# gemschematic_Chris_edits.net
KiCad netlist of a schematic drawn in Altium Designer
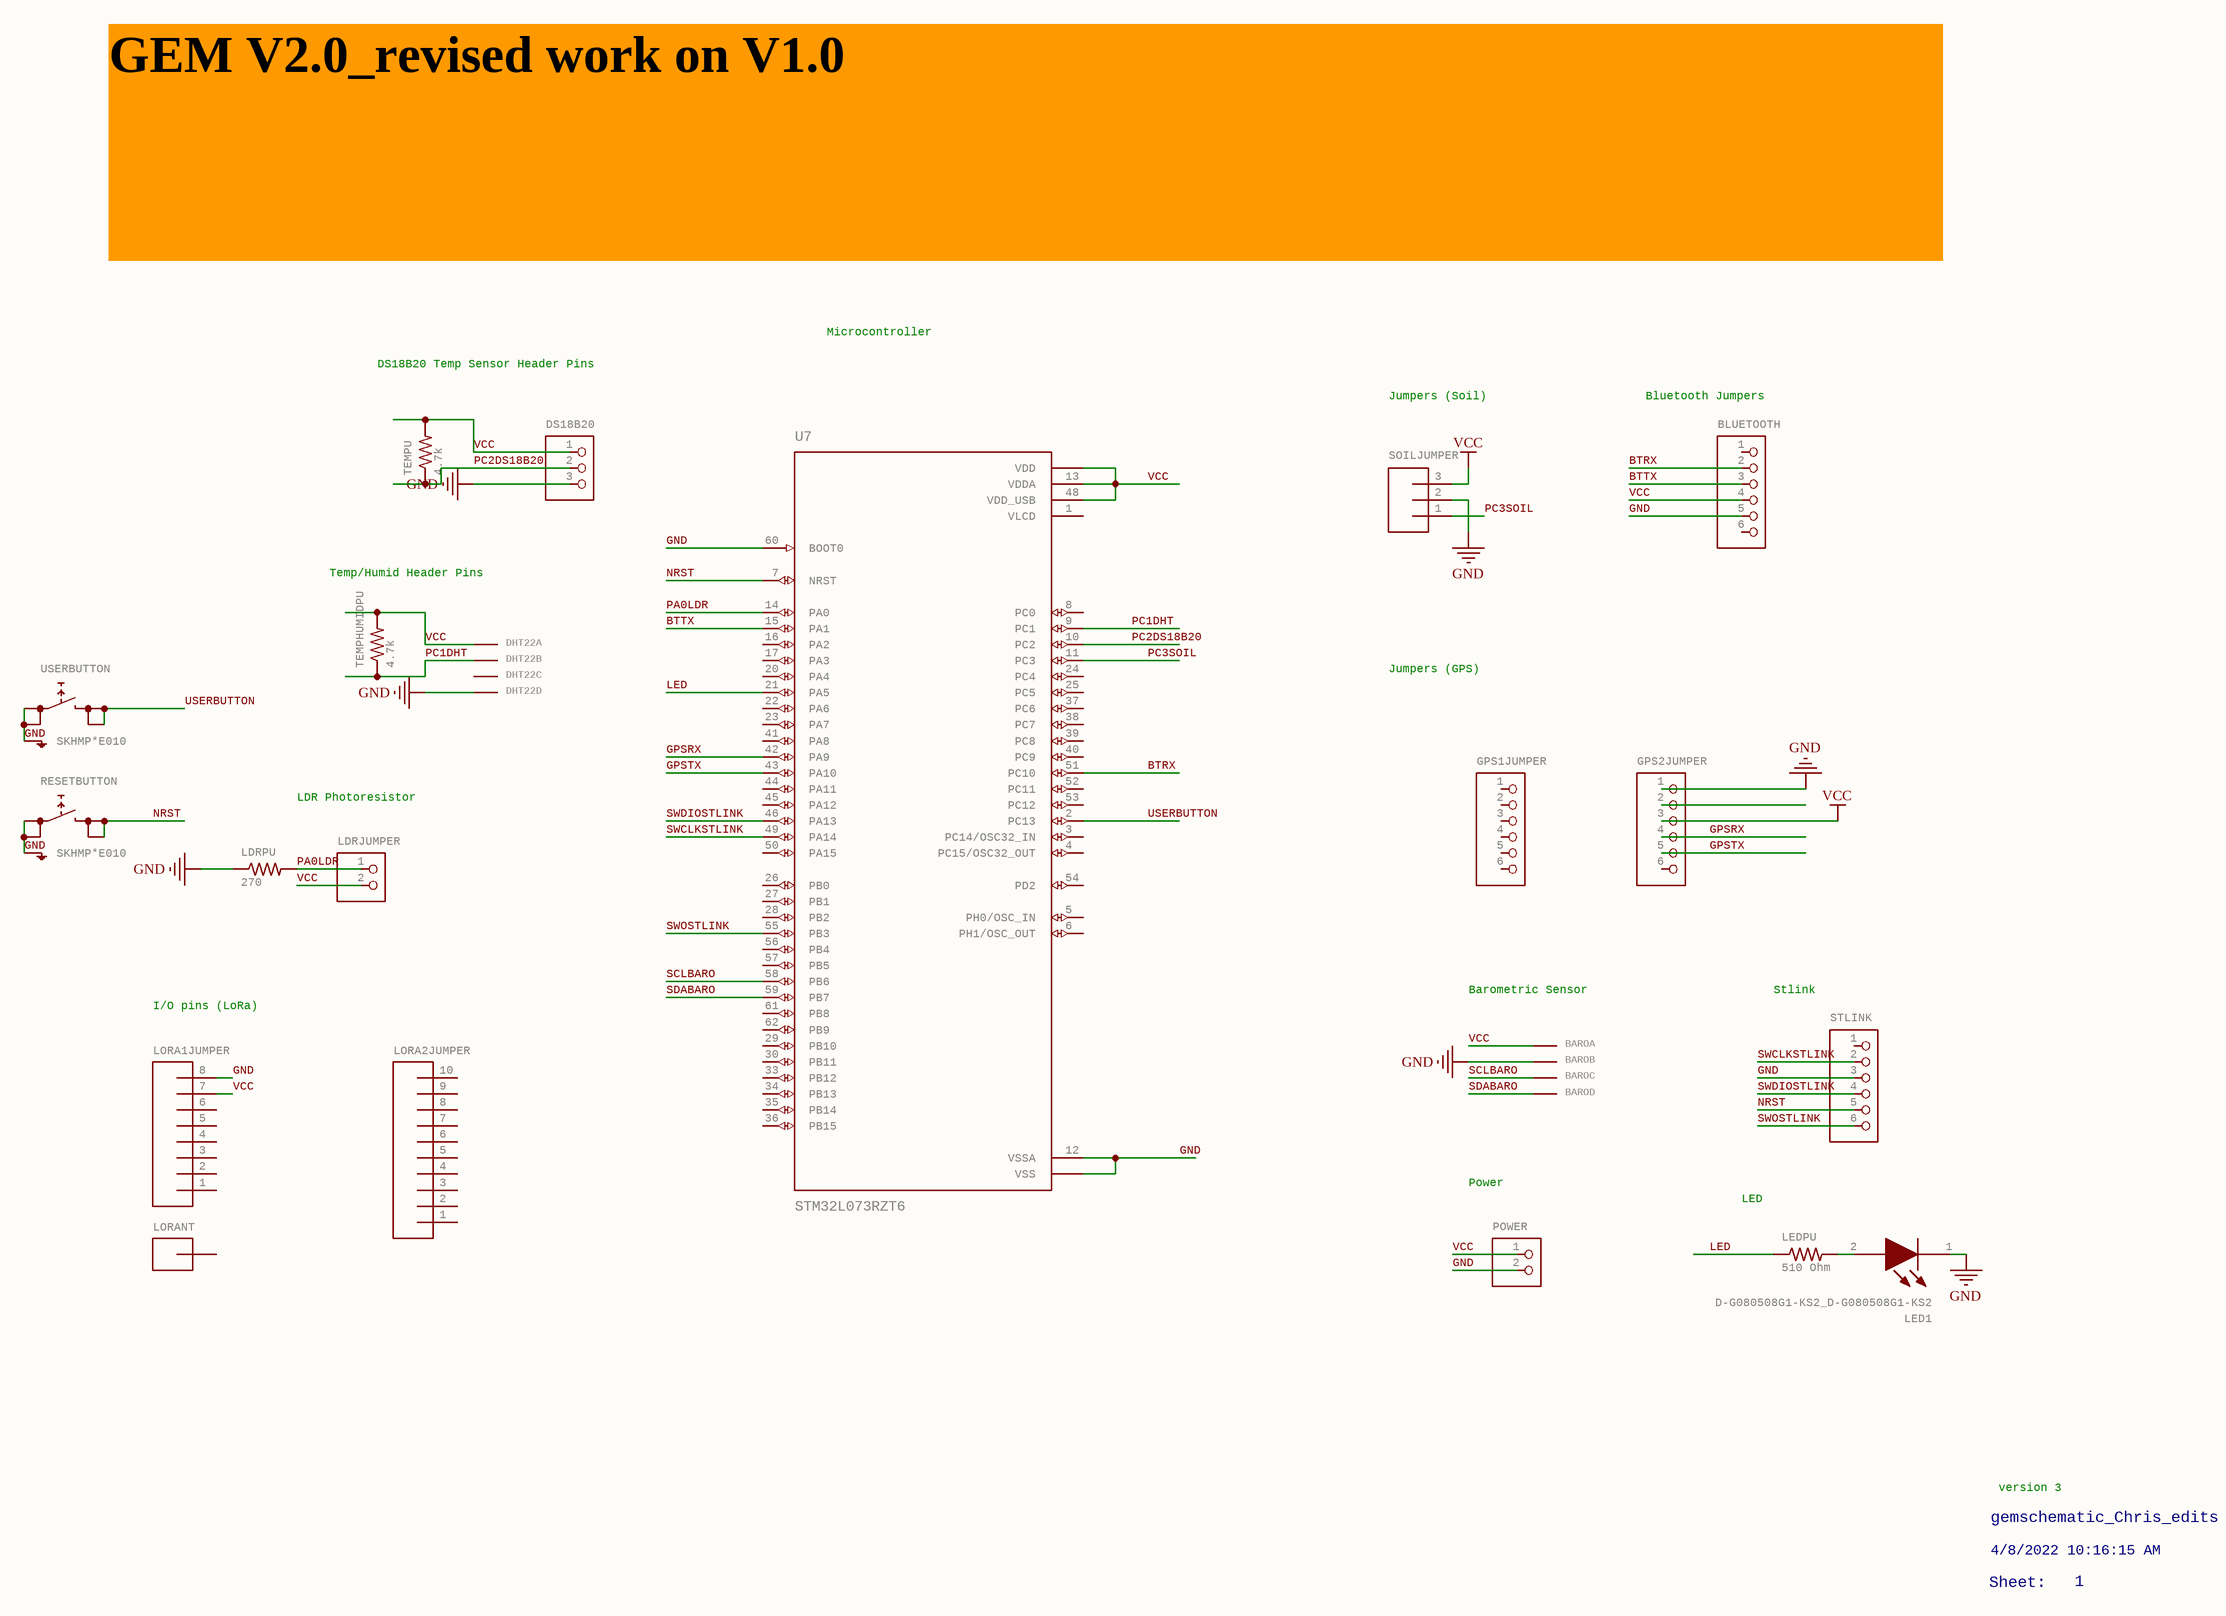
[diagram p0: gemschematic_Chris_edits.SchDoc]

(export (version "E")
  (design (tool "Eeschema 10.0.6"))
  (components
    (comp (ref "BARO")
      (value "22-23-2041")
      (footprint "22-23-2041")
      (description ".100\" (2.54mm) Center Header - 4 Pin")
      (fields (field (name "MF") "MOLEX"))
      (libsource (lib "con-molex") (part "22-23-2041"))
    )
    (comp (ref "BLUETOOTH")
      (value "PINHD-1X6")
      (footprint "1X06")
      (description "PIN HEADER")
      (libsource (lib "adafruit") (part "PINHD-1X6"))
    )
    (comp (ref "DHT22")
      (value "22-23-2041")
      (footprint "22-23-2041")
      (description ".100\" (2.54mm) Center Header - 4 Pin")
      (fields (field (name "MF") "MOLEX"))
      (libsource (lib "con-molex") (part "22-23-2041"))
    )
    (comp (ref "DS18B20")
      (value "PINHD-1X3")
      (footprint "1X03")
      (description "PIN HEADER")
      (libsource (lib "adafruit") (part "PINHD-1X3"))
    )
    (comp (ref "GPS1JUMPER")
      (value "HEADER-1X670MIL")
      (footprint "1X06_ROUND_70")
      (description "PIN HEADER")
      (libsource (lib "microbuilder") (part "HEADER-1X670MIL"))
    )
    (comp (ref "GPS2JUMPER")
      (value "HEADER-1X670MIL")
      (footprint "1X06_ROUND_70")
      (description "PIN HEADER")
      (libsource (lib "microbuilder") (part "HEADER-1X670MIL"))
    )
    (comp (ref "LDRJUMPER")
      (value "PINHD-1X2")
      (footprint "1X02")
      (description "PIN HEADER")
      (fields (field (name "LIBRARYNAME") "pinhead"))
      (libsource (lib "pinhead") (part "PINHD-1X2"))
    )
    (comp (ref "LDRPU")
      (value "270")
      (footprint "M0805")
      (description "RESISTOR, American symbol")
      (libsource (lib "adafruit") (part "R-US_M0805"))
    )
    (comp (ref "LED1")
      (value "D-G080508G1-KS2_D-G080508G1-KS2")
      (footprint "D-G080508G1-KS2_LEDC2012X85N")
      (description "Light Emitting Diodes (LED) Green 526~531nm 250~330mcd@5mA Top View 0805 RoHS   Source:  Datasheet")
      (fields
        (field (name "ARROW_PART_NUMBER") "ARROW_PART_NUMBER")
        (field (name "MANUFACTURER_PART_NUMBER") "D-G080508G1-KS2")
        (field (name "LIBRARYNAME") "ce-capstone-2022")
      )
      (libsource (lib "ce-capstone-2022") (part "D-G080508G1-KS2_D-G080508G1-KS2"))
    )
    (comp (ref "LEDPU")
      (value "510 Ohm")
      (footprint "M0805")
      (description "RESISTOR, American symbol")
      (libsource (lib "adafruit") (part "R-US_M0805"))
    )
    (comp (ref "LORA1JUMPER")
      (value "CONN_08NO_SILK_FEMALE_PTH")
      (footprint "1X08_NO_SILK")
      (libsource (lib "SparkFun-Connectors") (part "CONN_08NO_SILK_FEMALE_PTH"))
    )
    (comp (ref "LORA2JUMPER")
      (value "CONN_10NO_SILK_PTH_FEMALE")
      (footprint "1X10_NO_SILK")
      (libsource (lib "SparkFun-Connectors") (part "CONN_10NO_SILK_PTH_FEMALE"))
    )
    (comp (ref "LORANT")
      (value "CONN_01PTH_NO_SILK_YES_STOP")
      (footprint "1X01_NO_SILK")
      (libsource (lib "SparkFun-Connectors") (part "CONN_01PTH_NO_SILK_YES_STOP"))
    )
    (comp (ref "POWER")
      (value "PINHD-1X2")
      (footprint "1X02")
      (description "PIN HEADER")
      (fields (field (name "LIBRARYNAME") "pinhead"))
      (libsource (lib "pinhead") (part "PINHD-1X2"))
    )
    (comp (ref "RESETBUTTON")
      (value "SKHMP*E010")
      (footprint "SKHMPXE010")
      (libsource (lib "switch") (part "SKHMP*E010"))
    )
    (comp (ref "SOILJUMPER")
      (value "M03SCREW_LOCK")
      (footprint "SCREWTERMINAL-3.5MM-3_LOCK.007S")
      (libsource (lib "SparkFun-Connectors") (part "M03SCREW_LOCK"))
    )
    (comp (ref "STLINK")
      (value "PINHD-1X6")
      (footprint "1X06")
      (description "PIN HEADER")
      (libsource (lib "adafruit") (part "PINHD-1X6"))
    )
    (comp (ref "TEMPHUMIDPU")
      (value "4.7k")
      (footprint "M0805")
      (description "RESISTOR, American symbol")
      (libsource (lib "adafruit") (part "R-US_M0805"))
    )
    (comp (ref "TEMPU")
      (value "4.7k")
      (footprint "M0805")
      (description "RESISTOR, American symbol")
      (libsource (lib "adafruit") (part "R-US_M0805"))
    )
    (comp (ref "U7")
      (value "STM32L073RZT6")
      (footprint "QFP50P1200X1200X160-64N")
      (description "None Check availability")
      (fields (field (name "MF") "STMicroelectronics"))
      (libsource (lib "STM32L073RZT6") (part "STM32L073RZT6"))
    )
    (comp (ref "USERBUTTON")
      (value "SKHMP*E010")
      (footprint "SKHMPXE010")
      (libsource (lib "switch") (part "SKHMP*E010"))
    )
  )
  (nets
    (net (code "1") (name "/BTRX") (class "Default")
      (node (ref "BLUETOOTH") (pin "2") (pinfunction "2_2") (pintype "passive"))
      (node (ref "U7") (pin "51") (pinfunction "PC10_51") (pintype "bidirectional"))
    )
    (net (code "2") (name "/BTTX") (class "Default")
      (node (ref "BLUETOOTH") (pin "3") (pinfunction "3_3") (pintype "passive"))
      (node (ref "U7") (pin "15") (pinfunction "PA1_15") (pintype "bidirectional"))
    )
    (net (code "3") (name "/GPSRX") (class "Default")
      (node (ref "GPS2JUMPER") (pin "4") (pinfunction "4_4") (pintype "passive"))
      (node (ref "U7") (pin "42") (pinfunction "PA9_42") (pintype "bidirectional"))
    )
    (net (code "4") (name "/GPSTX") (class "Default")
      (node (ref "GPS2JUMPER") (pin "5") (pinfunction "5_5") (pintype "passive"))
      (node (ref "U7") (pin "43") (pinfunction "PA10_43") (pintype "bidirectional"))
    )
    (net (code "5") (name "/LED") (class "Default")
      (node (ref "LEDPU") (pin "1") (pinfunction "1_1") (pintype "passive"))
      (node (ref "U7") (pin "21") (pinfunction "PA5_21") (pintype "bidirectional"))
    )
    (net (code "6") (name "/NRST") (class "Default")
      (node (ref "RESETBUTTON") (pin "3") (pinfunction "2.1_3") (pintype "passive"))
      (node (ref "RESETBUTTON") (pin "4") (pinfunction "2.2_4") (pintype "passive"))
      (node (ref "STLINK") (pin "5") (pinfunction "5_5") (pintype "passive"))
      (node (ref "U7") (pin "7") (pinfunction "NRST_7") (pintype "bidirectional"))
    )
    (net (code "7") (name "/PA0LDR") (class "Default")
      (node (ref "LDRJUMPER") (pin "1") (pinfunction "1_1") (pintype "passive"))
      (node (ref "LDRPU") (pin "2") (pinfunction "2_2") (pintype "passive"))
      (node (ref "U7") (pin "14") (pinfunction "PA0_14") (pintype "bidirectional"))
    )
    (net (code "8") (name "/PC1DHT") (class "Default")
      (node (ref "DHT22") (pin "2") (pinfunction "S_2") (pintype "passive"))
      (node (ref "TEMPHUMIDPU") (pin "1") (pinfunction "1_1") (pintype "passive"))
      (node (ref "U7") (pin "9") (pinfunction "PC1_9") (pintype "bidirectional"))
    )
    (net (code "9") (name "/PC2DS18B20") (class "Default")
      (node (ref "DS18B20") (pin "2") (pinfunction "2_2") (pintype "passive"))
      (node (ref "TEMPU") (pin "1") (pinfunction "1_1") (pintype "passive"))
      (node (ref "U7") (pin "10") (pinfunction "PC2_10") (pintype "bidirectional"))
    )
    (net (code "10") (name "/PC3SOIL") (class "Default")
      (node (ref "SOILJUMPER") (pin "1") (pinfunction "1_1") (pintype "passive"))
      (node (ref "U7") (pin "11") (pinfunction "PC3_11") (pintype "bidirectional"))
    )
    (net (code "11") (name "/SCLBARO") (class "Default")
      (node (ref "BARO") (pin "3") (pinfunction "S_3") (pintype "passive"))
      (node (ref "U7") (pin "58") (pinfunction "PB6_58") (pintype "bidirectional"))
    )
    (net (code "12") (name "/SDABARO") (class "Default")
      (node (ref "BARO") (pin "4") (pinfunction "S_4") (pintype "passive"))
      (node (ref "U7") (pin "59") (pinfunction "PB7_59") (pintype "bidirectional"))
    )
    (net (code "13") (name "/SWCLKSTLINK") (class "Default")
      (node (ref "STLINK") (pin "2") (pinfunction "2_2") (pintype "passive"))
      (node (ref "U7") (pin "49") (pinfunction "PA14_49") (pintype "bidirectional"))
    )
    (net (code "14") (name "/SWDIOSTLINK") (class "Default")
      (node (ref "STLINK") (pin "4") (pinfunction "4_4") (pintype "passive"))
      (node (ref "U7") (pin "46") (pinfunction "PA13_46") (pintype "bidirectional"))
    )
    (net (code "15") (name "/SWOSTLINK") (class "Default")
      (node (ref "STLINK") (pin "6") (pinfunction "6_6") (pintype "passive"))
      (node (ref "U7") (pin "55") (pinfunction "PB3_55") (pintype "bidirectional"))
    )
    (net (code "16") (name "/USERBUTTON") (class "Default")
      (node (ref "U7") (pin "2") (pinfunction "PC13_2") (pintype "bidirectional"))
      (node (ref "USERBUTTON") (pin "3") (pinfunction "2.1_3") (pintype "passive"))
      (node (ref "USERBUTTON") (pin "4") (pinfunction "2.2_4") (pintype "passive"))
    )
    (net (code "17") (name "GND") (class "Default")
      (node (ref "BARO") (pin "2") (pinfunction "S_2") (pintype "passive"))
      (node (ref "BLUETOOTH") (pin "5") (pinfunction "5_5") (pintype "passive"))
      (node (ref "DHT22") (pin "4") (pinfunction "S_4") (pintype "passive"))
      (node (ref "DS18B20") (pin "3") (pinfunction "3_3") (pintype "passive"))
      (node (ref "GPS2JUMPER") (pin "1") (pinfunction "1_1") (pintype "passive"))
      (node (ref "LDRPU") (pin "1") (pinfunction "1_1") (pintype "passive"))
      (node (ref "LED1") (pin "1") (pinfunction "K_1") (pintype "bidirectional"))
      (node (ref "LORA1JUMPER") (pin "8") (pinfunction "8_8") (pintype "passive"))
      (node (ref "POWER") (pin "2") (pinfunction "2_2") (pintype "passive"))
      (node (ref "RESETBUTTON") (pin "1") (pinfunction "1.1_1") (pintype "passive"))
      (node (ref "RESETBUTTON") (pin "2") (pinfunction "1.2_2") (pintype "passive"))
      (node (ref "RESETBUTTON") (pin "5") (pinfunction "SH_5") (pintype "passive"))
      (node (ref "SOILJUMPER") (pin "2") (pinfunction "2_2") (pintype "passive"))
      (node (ref "STLINK") (pin "3") (pinfunction "3_3") (pintype "passive"))
      (node (ref "U7") (pin "12") (pinfunction "VSSA_12") (pintype "power_in"))
      (node (ref "U7") (pin "18_31_47_63") (pinfunction "VSS_18_31_47_63") (pintype "power_in"))
      (node (ref "U7") (pin "60") (pinfunction "BOOT0_60") (pintype "input"))
      (node (ref "USERBUTTON") (pin "1") (pinfunction "1.1_1") (pintype "passive"))
      (node (ref "USERBUTTON") (pin "2") (pinfunction "1.2_2") (pintype "passive"))
      (node (ref "USERBUTTON") (pin "5") (pinfunction "SH_5") (pintype "passive"))
    )
    (net (code "18") (name "Net-(LED1-A)") (class "Default")
      (node (ref "LED1") (pin "2") (pinfunction "A_2") (pintype "bidirectional"))
      (node (ref "LEDPU") (pin "2") (pinfunction "2_2") (pintype "passive"))
    )
    (net (code "19") (name "VCC") (class "Default")
      (node (ref "BARO") (pin "1") (pinfunction "S_1") (pintype "passive"))
      (node (ref "BLUETOOTH") (pin "4") (pinfunction "4_4") (pintype "passive"))
      (node (ref "DHT22") (pin "1") (pinfunction "S_1") (pintype "passive"))
      (node (ref "DS18B20") (pin "1") (pinfunction "1_1") (pintype "passive"))
      (node (ref "GPS2JUMPER") (pin "3") (pinfunction "3_3") (pintype "passive"))
      (node (ref "LDRJUMPER") (pin "2") (pinfunction "2_2") (pintype "passive"))
      (node (ref "LORA1JUMPER") (pin "7") (pinfunction "7_7") (pintype "passive"))
      (node (ref "POWER") (pin "1") (pinfunction "1_1") (pintype "passive"))
      (node (ref "SOILJUMPER") (pin "3") (pinfunction "3_3") (pintype "passive"))
      (node (ref "TEMPHUMIDPU") (pin "2") (pinfunction "2_2") (pintype "passive"))
      (node (ref "TEMPU") (pin "2") (pinfunction "2_2") (pintype "passive"))
      (node (ref "U7") (pin "13") (pinfunction "VDDA_13") (pintype "power_in"))
      (node (ref "U7") (pin "19_32_64") (pinfunction "VDD_19_32_64") (pintype "power_in"))
      (node (ref "U7") (pin "48") (pinfunction "VDD_USB_48") (pintype "power_in"))
    )
    (net (code "20") (name "unconnected-(BLUETOOTH-Pad1)") (class "Default")
      (node (ref "BLUETOOTH") (pin "1") (pinfunction "1_1") (pintype "passive"))
    )
    (net (code "21") (name "unconnected-(BLUETOOTH-Pad6)") (class "Default")
      (node (ref "BLUETOOTH") (pin "6") (pinfunction "6_6") (pintype "passive"))
    )
    (net (code "22") (name "unconnected-(DHT22C-S-Pad3)") (class "Default")
      (node (ref "DHT22") (pin "3") (pinfunction "S_3") (pintype "passive"))
    )
    (net (code "23") (name "unconnected-(GPS1JUMPER-Pad1)") (class "Default")
      (node (ref "GPS1JUMPER") (pin "1") (pinfunction "1_1") (pintype "passive"))
    )
    (net (code "24") (name "unconnected-(GPS1JUMPER-Pad2)") (class "Default")
      (node (ref "GPS1JUMPER") (pin "2") (pinfunction "2_2") (pintype "passive"))
    )
    (net (code "25") (name "unconnected-(GPS1JUMPER-Pad3)") (class "Default")
      (node (ref "GPS1JUMPER") (pin "3") (pinfunction "3_3") (pintype "passive"))
    )
    (net (code "26") (name "unconnected-(GPS1JUMPER-Pad4)") (class "Default")
      (node (ref "GPS1JUMPER") (pin "4") (pinfunction "4_4") (pintype "passive"))
    )
    (net (code "27") (name "unconnected-(GPS1JUMPER-Pad5)") (class "Default")
      (node (ref "GPS1JUMPER") (pin "5") (pinfunction "5_5") (pintype "passive"))
    )
    (net (code "28") (name "unconnected-(GPS1JUMPER-Pad6)") (class "Default")
      (node (ref "GPS1JUMPER") (pin "6") (pinfunction "6_6") (pintype "passive"))
    )
    (net (code "29") (name "unconnected-(GPS2JUMPER-Pad2)") (class "Default")
      (node (ref "GPS2JUMPER") (pin "2") (pinfunction "2_2") (pintype "passive"))
    )
    (net (code "30") (name "unconnected-(GPS2JUMPER-Pad6)") (class "Default")
      (node (ref "GPS2JUMPER") (pin "6") (pinfunction "6_6") (pintype "passive"))
    )
    (net (code "31") (name "unconnected-(LORA1JUMPER-Pad1)") (class "Default")
      (node (ref "LORA1JUMPER") (pin "1") (pinfunction "1_1") (pintype "passive"))
    )
    (net (code "32") (name "unconnected-(LORA1JUMPER-Pad2)") (class "Default")
      (node (ref "LORA1JUMPER") (pin "2") (pinfunction "2_2") (pintype "passive"))
    )
    (net (code "33") (name "unconnected-(LORA1JUMPER-Pad3)") (class "Default")
      (node (ref "LORA1JUMPER") (pin "3") (pinfunction "3_3") (pintype "passive"))
    )
    (net (code "34") (name "unconnected-(LORA1JUMPER-Pad4)") (class "Default")
      (node (ref "LORA1JUMPER") (pin "4") (pinfunction "4_4") (pintype "passive"))
    )
    (net (code "35") (name "unconnected-(LORA1JUMPER-Pad5)") (class "Default")
      (node (ref "LORA1JUMPER") (pin "5") (pinfunction "5_5") (pintype "passive"))
    )
    (net (code "36") (name "unconnected-(LORA1JUMPER-Pad6)") (class "Default")
      (node (ref "LORA1JUMPER") (pin "6") (pinfunction "6_6") (pintype "passive"))
    )
    (net (code "37") (name "unconnected-(LORA2JUMPER-Pad1)") (class "Default")
      (node (ref "LORA2JUMPER") (pin "1") (pinfunction "1_1") (pintype "passive"))
    )
    (net (code "38") (name "unconnected-(LORA2JUMPER-Pad2)") (class "Default")
      (node (ref "LORA2JUMPER") (pin "2") (pinfunction "2_2") (pintype "passive"))
    )
    (net (code "39") (name "unconnected-(LORA2JUMPER-Pad3)") (class "Default")
      (node (ref "LORA2JUMPER") (pin "3") (pinfunction "3_3") (pintype "passive"))
    )
    (net (code "40") (name "unconnected-(LORA2JUMPER-Pad4)") (class "Default")
      (node (ref "LORA2JUMPER") (pin "4") (pinfunction "4_4") (pintype "passive"))
    )
    (net (code "41") (name "unconnected-(LORA2JUMPER-Pad5)") (class "Default")
      (node (ref "LORA2JUMPER") (pin "5") (pinfunction "5_5") (pintype "passive"))
    )
    (net (code "42") (name "unconnected-(LORA2JUMPER-Pad6)") (class "Default")
      (node (ref "LORA2JUMPER") (pin "6") (pinfunction "6_6") (pintype "passive"))
    )
    (net (code "43") (name "unconnected-(LORA2JUMPER-Pad7)") (class "Default")
      (node (ref "LORA2JUMPER") (pin "7") (pinfunction "7_7") (pintype "passive"))
    )
    (net (code "44") (name "unconnected-(LORA2JUMPER-Pad8)") (class "Default")
      (node (ref "LORA2JUMPER") (pin "8") (pinfunction "8_8") (pintype "passive"))
    )
    (net (code "45") (name "unconnected-(LORA2JUMPER-Pad9)") (class "Default")
      (node (ref "LORA2JUMPER") (pin "9") (pinfunction "9_9") (pintype "passive"))
    )
    (net (code "46") (name "unconnected-(LORA2JUMPER-Pad10)") (class "Default")
      (node (ref "LORA2JUMPER") (pin "10") (pinfunction "10_10") (pintype "passive"))
    )
    (net (code "47") (name "unconnected-(LORANT-Pad1)") (class "Default")
      (node (ref "LORANT") (pin "1") (pinfunction "1_1") (pintype "passive"))
    )
    (net (code "48") (name "unconnected-(STLINK-Pad1)") (class "Default")
      (node (ref "STLINK") (pin "1") (pinfunction "1_1") (pintype "passive"))
    )
    (net (code "49") (name "unconnected-(U7-PA2-Pad16)") (class "Default")
      (node (ref "U7") (pin "16") (pinfunction "PA2_16") (pintype "bidirectional"))
    )
    (net (code "50") (name "unconnected-(U7-PA3-Pad17)") (class "Default")
      (node (ref "U7") (pin "17") (pinfunction "PA3_17") (pintype "bidirectional"))
    )
    (net (code "51") (name "unconnected-(U7-PA4-Pad20)") (class "Default")
      (node (ref "U7") (pin "20") (pinfunction "PA4_20") (pintype "bidirectional"))
    )
    (net (code "52") (name "unconnected-(U7-PA6-Pad22)") (class "Default")
      (node (ref "U7") (pin "22") (pinfunction "PA6_22") (pintype "bidirectional"))
    )
    (net (code "53") (name "unconnected-(U7-PA7-Pad23)") (class "Default")
      (node (ref "U7") (pin "23") (pinfunction "PA7_23") (pintype "bidirectional"))
    )
    (net (code "54") (name "unconnected-(U7-PA8-Pad41)") (class "Default")
      (node (ref "U7") (pin "41") (pinfunction "PA8_41") (pintype "bidirectional"))
    )
    (net (code "55") (name "unconnected-(U7-PA11-Pad44)") (class "Default")
      (node (ref "U7") (pin "44") (pinfunction "PA11_44") (pintype "bidirectional"))
    )
    (net (code "56") (name "unconnected-(U7-PA12-Pad45)") (class "Default")
      (node (ref "U7") (pin "45") (pinfunction "PA12_45") (pintype "bidirectional"))
    )
    (net (code "57") (name "unconnected-(U7-PA15-Pad50)") (class "Default")
      (node (ref "U7") (pin "50") (pinfunction "PA15_50") (pintype "bidirectional"))
    )
    (net (code "58") (name "unconnected-(U7-PB0-Pad26)") (class "Default")
      (node (ref "U7") (pin "26") (pinfunction "PB0_26") (pintype "bidirectional"))
    )
    (net (code "59") (name "unconnected-(U7-PB1-Pad27)") (class "Default")
      (node (ref "U7") (pin "27") (pinfunction "PB1_27") (pintype "bidirectional"))
    )
    (net (code "60") (name "unconnected-(U7-PB2-Pad28)") (class "Default")
      (node (ref "U7") (pin "28") (pinfunction "PB2_28") (pintype "bidirectional"))
    )
    (net (code "61") (name "unconnected-(U7-PB4-Pad56)") (class "Default")
      (node (ref "U7") (pin "56") (pinfunction "PB4_56") (pintype "bidirectional"))
    )
    (net (code "62") (name "unconnected-(U7-PB5-Pad57)") (class "Default")
      (node (ref "U7") (pin "57") (pinfunction "PB5_57") (pintype "bidirectional"))
    )
    (net (code "63") (name "unconnected-(U7-PB8-Pad61)") (class "Default")
      (node (ref "U7") (pin "61") (pinfunction "PB8_61") (pintype "bidirectional"))
    )
    (net (code "64") (name "unconnected-(U7-PB9-Pad62)") (class "Default")
      (node (ref "U7") (pin "62") (pinfunction "PB9_62") (pintype "bidirectional"))
    )
    (net (code "65") (name "unconnected-(U7-PB10-Pad29)") (class "Default")
      (node (ref "U7") (pin "29") (pinfunction "PB10_29") (pintype "bidirectional"))
    )
    (net (code "66") (name "unconnected-(U7-PB11-Pad30)") (class "Default")
      (node (ref "U7") (pin "30") (pinfunction "PB11_30") (pintype "bidirectional"))
    )
    (net (code "67") (name "unconnected-(U7-PB12-Pad33)") (class "Default")
      (node (ref "U7") (pin "33") (pinfunction "PB12_33") (pintype "bidirectional"))
    )
    (net (code "68") (name "unconnected-(U7-PB13-Pad34)") (class "Default")
      (node (ref "U7") (pin "34") (pinfunction "PB13_34") (pintype "bidirectional"))
    )
    (net (code "69") (name "unconnected-(U7-PB14-Pad35)") (class "Default")
      (node (ref "U7") (pin "35") (pinfunction "PB14_35") (pintype "bidirectional"))
    )
    (net (code "70") (name "unconnected-(U7-PB15-Pad36)") (class "Default")
      (node (ref "U7") (pin "36") (pinfunction "PB15_36") (pintype "bidirectional"))
    )
    (net (code "71") (name "unconnected-(U7-PC0-Pad8)") (class "Default")
      (node (ref "U7") (pin "8") (pinfunction "PC0_8") (pintype "bidirectional"))
    )
    (net (code "72") (name "unconnected-(U7-PC4-Pad24)") (class "Default")
      (node (ref "U7") (pin "24") (pinfunction "PC4_24") (pintype "bidirectional"))
    )
    (net (code "73") (name "unconnected-(U7-PC5-Pad25)") (class "Default")
      (node (ref "U7") (pin "25") (pinfunction "PC5_25") (pintype "bidirectional"))
    )
    (net (code "74") (name "unconnected-(U7-PC6-Pad37)") (class "Default")
      (node (ref "U7") (pin "37") (pinfunction "PC6_37") (pintype "bidirectional"))
    )
    (net (code "75") (name "unconnected-(U7-PC7-Pad38)") (class "Default")
      (node (ref "U7") (pin "38") (pinfunction "PC7_38") (pintype "bidirectional"))
    )
    (net (code "76") (name "unconnected-(U7-PC8-Pad39)") (class "Default")
      (node (ref "U7") (pin "39") (pinfunction "PC8_39") (pintype "bidirectional"))
    )
    (net (code "77") (name "unconnected-(U7-PC9-Pad40)") (class "Default")
      (node (ref "U7") (pin "40") (pinfunction "PC9_40") (pintype "bidirectional"))
    )
    (net (code "78") (name "unconnected-(U7-PC11-Pad52)") (class "Default")
      (node (ref "U7") (pin "52") (pinfunction "PC11_52") (pintype "bidirectional"))
    )
    (net (code "79") (name "unconnected-(U7-PC12-Pad53)") (class "Default")
      (node (ref "U7") (pin "53") (pinfunction "PC12_53") (pintype "bidirectional"))
    )
    (net (code "80") (name "unconnected-(U7-PC14{slash}OSC32_IN-Pad3)") (class "Default")
      (node (ref "U7") (pin "3") (pinfunction "PC14/OSC32_IN_3") (pintype "bidirectional"))
    )
    (net (code "81") (name "unconnected-(U7-PC15{slash}OSC32_OUT-Pad4)") (class "Default")
      (node (ref "U7") (pin "4") (pinfunction "PC15/OSC32_OUT_4") (pintype "bidirectional"))
    )
    (net (code "82") (name "unconnected-(U7-PD2-Pad54)") (class "Default")
      (node (ref "U7") (pin "54") (pinfunction "PD2_54") (pintype "bidirectional"))
    )
    (net (code "83") (name "unconnected-(U7-PH0{slash}OSC_IN-Pad5)") (class "Default")
      (node (ref "U7") (pin "5") (pinfunction "PH0/OSC_IN_5") (pintype "bidirectional"))
    )
    (net (code "84") (name "unconnected-(U7-PH1{slash}OSC_OUT-Pad6)") (class "Default")
      (node (ref "U7") (pin "6") (pinfunction "PH1/OSC_OUT_6") (pintype "bidirectional"))
    )
    (net (code "85") (name "unconnected-(U7-VLCD-Pad1)") (class "Default")
      (node (ref "U7") (pin "1") (pinfunction "VLCD_1") (pintype "power_in"))
    )
  )
)
